# sch.net
KiCad netlist of a schematic drawn in Altium Designer
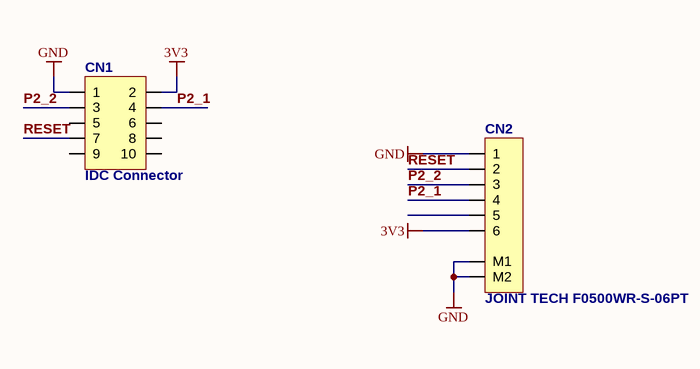
[diagram p0: sch.SchDoc]

(export (version "E")
  (design (tool "Eeschema 10.0.6"))
  (components
    (comp (ref "CN1") (value "IDC Connector") (footprint "IDC10") (libsource (lib "idc") (part "CN_5x2")))
    (comp (ref "CN2")
      (value "JOINT TECH F0500WR-S-06PT")
      (footprint "F0500WR-S-06PT")
      (description "0.50mm Pitch FFC/FPC Connector, SMT, Right Angle, ZIF, Top Contact Style Receptacle, 6 Circuits")
      (libsource (lib "ffc_fpc") (part "JOINT TECH F0500WR-S-06PT"))
    )
  )
  (nets
    (net (code "1") (name "/P2_1") (class "Default")
      (node (ref "CN1") (pin "4") (pinfunction "4_4") (pintype "passive"))
      (node (ref "CN2") (pin "4") (pinfunction "4_4") (pintype "passive"))
    )
    (net (code "2") (name "/P2_2") (class "Default")
      (node (ref "CN1") (pin "3") (pinfunction "3_3") (pintype "passive"))
      (node (ref "CN2") (pin "3") (pinfunction "3_3") (pintype "passive"))
    )
    (net (code "3") (name "/RESET") (class "Default")
      (node (ref "CN1") (pin "7") (pinfunction "7_7") (pintype "passive"))
      (node (ref "CN2") (pin "2") (pinfunction "2_2") (pintype "passive"))
    )
    (net (code "4") (name "3V3") (class "Default")
      (node (ref "CN1") (pin "2") (pinfunction "2_2") (pintype "passive"))
      (node (ref "CN2") (pin "6") (pinfunction "6_6") (pintype "passive"))
    )
    (net (code "5") (name "GND") (class "Default")
      (node (ref "CN1") (pin "1") (pinfunction "1_1") (pintype "passive"))
      (node (ref "CN2") (pin "1") (pinfunction "1_1") (pintype "passive"))
      (node (ref "CN2") (pin "10") (pinfunction "M2_10") (pintype "passive"))
      (node (ref "CN2") (pin "9") (pinfunction "M1_9") (pintype "passive"))
    )
    (net (code "6") (name "unconnected-(CN1-Pad5)") (class "Default")
      (node (ref "CN1") (pin "5") (pinfunction "5_5") (pintype "passive"))
    )
    (net (code "7") (name "unconnected-(CN1-Pad6)") (class "Default")
      (node (ref "CN1") (pin "6") (pinfunction "6_6") (pintype "passive"))
    )
    (net (code "8") (name "unconnected-(CN1-Pad8)") (class "Default")
      (node (ref "CN1") (pin "8") (pinfunction "8_8") (pintype "passive"))
    )
    (net (code "9") (name "unconnected-(CN1-Pad9)") (class "Default")
      (node (ref "CN1") (pin "9") (pinfunction "9_9") (pintype "passive"))
    )
    (net (code "10") (name "unconnected-(CN1-Pad10)") (class "Default")
      (node (ref "CN1") (pin "10") (pinfunction "10_10") (pintype "passive"))
    )
    (net (code "11") (name "unconnected-(CN2-Pad5)") (class "Default")
      (node (ref "CN2") (pin "5") (pinfunction "5_5") (pintype "passive"))
    )
  )
)
